# mega328_withheaders_andxbee.net
KiCad netlist of a schematic drawn in EAGLE
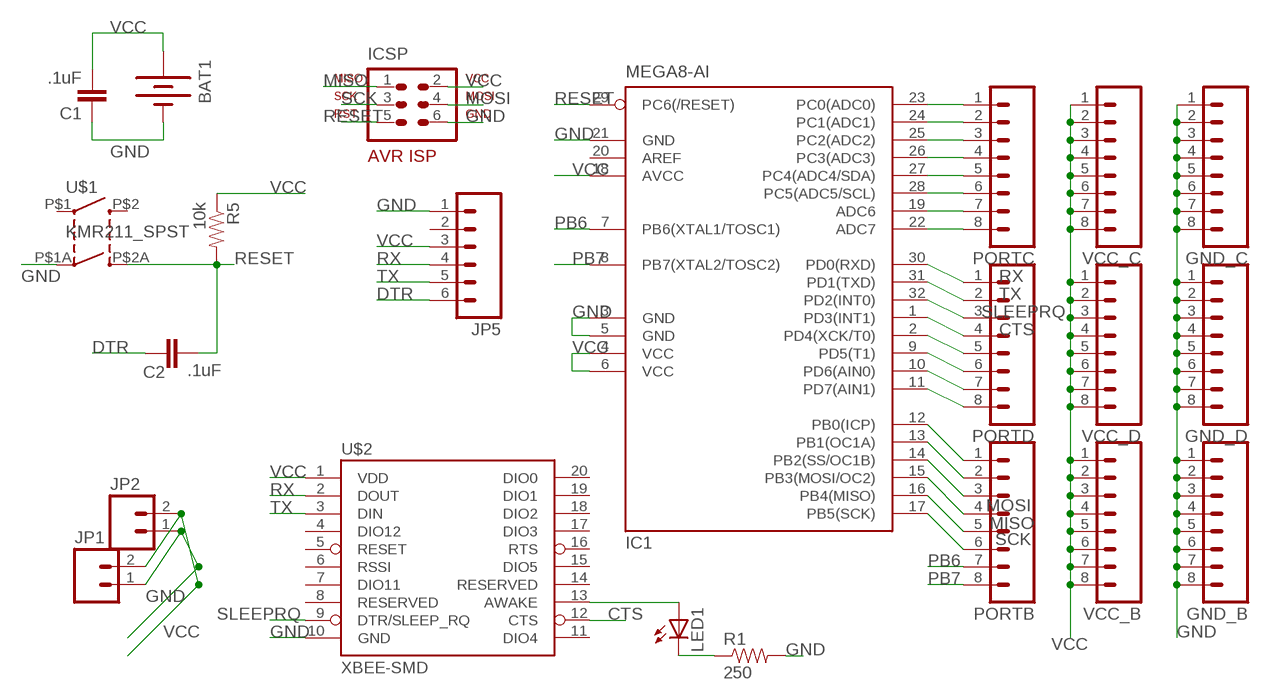
[diagram p0: schematic, sheet 1]

(export (version "E")
  (design (tool "Eeschema 10.0.6"))
  (components
    (comp (ref "BAT1")
      (value "BATTERY20SMD")
      (footprint "eagle-import:BATTCON_20MM")
      (libsource (lib "eagle-import") (part "BATTERY20SMD"))
    )
    (comp (ref "C1")
      (value ".1uF")
      (footprint "eagle-import:0603-CAP")
      (libsource (lib "eagle-import") (part "CAP0603-CAP"))
    )
    (comp (ref "C2")
      (value ".1uF")
      (footprint "eagle-import:0603-CAP")
      (libsource (lib "eagle-import") (part "CAP0603-CAP"))
    )
    (comp (ref "GND_B")
      (value "M081X08")
      (footprint "eagle-import:1X08")
      (libsource (lib "eagle-import") (part "M081X08"))
    )
    (comp (ref "GND_C")
      (value "M081X08")
      (footprint "eagle-import:1X08")
      (libsource (lib "eagle-import") (part "M081X08"))
    )
    (comp (ref "GND_D")
      (value "M081X08")
      (footprint "eagle-import:1X08")
      (libsource (lib "eagle-import") (part "M081X08"))
    )
    (comp (ref "IC1")
      (value "MEGA8-AI")
      (footprint "eagle-import:TQFP32-08")
      (fields (field (name "MPN") "ATMEGA8-16AU"))
      (libsource (lib "eagle-import") (part "MEGA8-AI"))
    )
    (comp (ref "ICSP")
      (value "ISP")
      (footprint "eagle-import:AVR-ISP-6")
      (libsource (lib "eagle-import") (part "AVR-ISP-6VERT"))
    )
    (comp (ref "JP1")
      (value "M02PTH")
      (footprint "eagle-import:1X02")
      (libsource (lib "eagle-import") (part "M02PTH"))
    )
    (comp (ref "JP2")
      (value "M02PTH")
      (footprint "eagle-import:1X02")
      (libsource (lib "eagle-import") (part "M02PTH"))
    )
    (comp (ref "JP5")
      (value "M06SIP")
      (footprint "eagle-import:1X06")
      (libsource (lib "eagle-import") (part "M06SIP"))
    )
    (comp (ref "LED1")
      (value "LEDCHIP-LED0603")
      (footprint "eagle-import:CHIP-LED0603")
      (libsource (lib "eagle-import") (part "LEDCHIP-LED0603"))
    )
    (comp (ref "PORTB")
      (value "M081X08")
      (footprint "eagle-import:1X08")
      (libsource (lib "eagle-import") (part "M081X08"))
    )
    (comp (ref "PORTC")
      (value "M081X08")
      (footprint "eagle-import:1X08")
      (libsource (lib "eagle-import") (part "M081X08"))
    )
    (comp (ref "PORTD")
      (value "M081X08")
      (footprint "eagle-import:1X08")
      (libsource (lib "eagle-import") (part "M081X08"))
    )
    (comp (ref "R1")
      (value "250")
      (footprint "eagle-import:0603-RES")
      (libsource (lib "eagle-import") (part "my library_RESISTOR0603-RES"))
    )
    (comp (ref "R5")
      (value "10k")
      (footprint "eagle-import:0603-RES")
      (libsource (lib "eagle-import") (part "RESISTOR0603-RES"))
    )
    (comp (ref "U$1")
      (value "KMR211_SPST")
      (footprint "eagle-import:KMR211_SPST")
      (libsource (lib "eagle-import") (part "KMR211_SPST"))
    )
    (comp (ref "U$2")
      (value "XBEE-SMD")
      (footprint "eagle-import:XBEE-SMD")
      (libsource (lib "eagle-import") (part "XBEE-SMD"))
    )
    (comp (ref "VCC_B")
      (value "M081X08")
      (footprint "eagle-import:1X08")
      (libsource (lib "eagle-import") (part "M081X08"))
    )
    (comp (ref "VCC_C")
      (value "M081X08")
      (footprint "eagle-import:1X08")
      (libsource (lib "eagle-import") (part "M081X08"))
    )
    (comp (ref "VCC_D")
      (value "M081X08")
      (footprint "eagle-import:1X08")
      (libsource (lib "eagle-import") (part "M081X08"))
    )
  )
  (nets
    (net (code "1") (name "/CTS") (class "Default")
      (node (ref "IC1") (pin "1") (pinfunction "PD3(INT1)_1") (pintype "bidirectional"))
      (node (ref "PORTD") (pin "4") (pinfunction "4_4") (pintype "passive"))
      (node (ref "U$2") (pin "12") (pinfunction "CTS_12") (pintype "output"))
    )
    (net (code "2") (name "/DTR") (class "Default")
      (node (ref "C2") (pin "1") (pinfunction "1_1") (pintype "passive"))
      (node (ref "JP5") (pin "6") (pinfunction "6_6") (pintype "passive"))
    )
    (net (code "3") (name "/GND") (class "Default")
      (node (ref "BAT1") (pin "2") (pinfunction "-_2") (pintype "power_in"))
      (node (ref "C1") (pin "1") (pinfunction "1_1") (pintype "passive"))
      (node (ref "GND_B") (pin "1") (pinfunction "1_1") (pintype "passive"))
      (node (ref "GND_B") (pin "2") (pinfunction "2_2") (pintype "passive"))
      (node (ref "GND_B") (pin "3") (pinfunction "3_3") (pintype "passive"))
      (node (ref "GND_B") (pin "4") (pinfunction "4_4") (pintype "passive"))
      (node (ref "GND_B") (pin "5") (pinfunction "5_5") (pintype "passive"))
      (node (ref "GND_B") (pin "6") (pinfunction "6_6") (pintype "passive"))
      (node (ref "GND_B") (pin "7") (pinfunction "7_7") (pintype "passive"))
      (node (ref "GND_B") (pin "8") (pinfunction "8_8") (pintype "passive"))
      (node (ref "GND_C") (pin "1") (pinfunction "1_1") (pintype "passive"))
      (node (ref "GND_C") (pin "2") (pinfunction "2_2") (pintype "passive"))
      (node (ref "GND_C") (pin "3") (pinfunction "3_3") (pintype "passive"))
      (node (ref "GND_C") (pin "4") (pinfunction "4_4") (pintype "passive"))
      (node (ref "GND_C") (pin "5") (pinfunction "5_5") (pintype "passive"))
      (node (ref "GND_C") (pin "6") (pinfunction "6_6") (pintype "passive"))
      (node (ref "GND_C") (pin "7") (pinfunction "7_7") (pintype "passive"))
      (node (ref "GND_C") (pin "8") (pinfunction "8_8") (pintype "passive"))
      (node (ref "GND_D") (pin "1") (pinfunction "1_1") (pintype "passive"))
      (node (ref "GND_D") (pin "2") (pinfunction "2_2") (pintype "passive"))
      (node (ref "GND_D") (pin "3") (pinfunction "3_3") (pintype "passive"))
      (node (ref "GND_D") (pin "4") (pinfunction "4_4") (pintype "passive"))
      (node (ref "GND_D") (pin "5") (pinfunction "5_5") (pintype "passive"))
      (node (ref "GND_D") (pin "6") (pinfunction "6_6") (pintype "passive"))
      (node (ref "GND_D") (pin "7") (pinfunction "7_7") (pintype "passive"))
      (node (ref "GND_D") (pin "8") (pinfunction "8_8") (pintype "passive"))
      (node (ref "IC1") (pin "21") (pinfunction "GND_21") (pintype "power_in"))
      (node (ref "IC1") (pin "3") (pinfunction "GND_3") (pintype "power_in"))
      (node (ref "IC1") (pin "5") (pinfunction "GND_5") (pintype "power_in"))
      (node (ref "ICSP") (pin "6") (pinfunction "6_6") (pintype "passive"))
      (node (ref "JP1") (pin "1") (pinfunction "1_1") (pintype "passive"))
      (node (ref "JP2") (pin "1") (pinfunction "1_1") (pintype "passive"))
      (node (ref "JP5") (pin "1") (pinfunction "1_1") (pintype "passive"))
      (node (ref "R1") (pin "2") (pinfunction "2_2") (pintype "passive"))
      (node (ref "U$1") (pin "P$1A") (pinfunction "1B_P$1A") (pintype "passive"))
      (node (ref "U$2") (pin "10") (pinfunction "GND_10") (pintype "power_in"))
    )
    (net (code "4") (name "/MISO") (class "Default")
      (node (ref "IC1") (pin "16") (pinfunction "PB4(MISO)_16") (pintype "bidirectional"))
      (node (ref "ICSP") (pin "1") (pinfunction "1_1") (pintype "passive"))
      (node (ref "PORTB") (pin "5") (pinfunction "5_5") (pintype "passive"))
    )
    (net (code "5") (name "/MOSI") (class "Default")
      (node (ref "IC1") (pin "15") (pinfunction "PB3(MOSI/OC2)_15") (pintype "bidirectional"))
      (node (ref "ICSP") (pin "4") (pinfunction "4_4") (pintype "passive"))
      (node (ref "PORTB") (pin "4") (pinfunction "4_4") (pintype "passive"))
    )
    (net (code "6") (name "/PB6") (class "Default")
      (node (ref "IC1") (pin "7") (pinfunction "PB6(XTAL1/TOSC1)_7") (pintype "bidirectional"))
      (node (ref "PORTB") (pin "7") (pinfunction "7_7") (pintype "passive"))
    )
    (net (code "7") (name "/PB7") (class "Default")
      (node (ref "IC1") (pin "8") (pinfunction "PB7(XTAL2/TOSC2)_8") (pintype "bidirectional"))
      (node (ref "PORTB") (pin "8") (pinfunction "8_8") (pintype "passive"))
    )
    (net (code "8") (name "/RESET") (class "Default")
      (node (ref "C2") (pin "2") (pinfunction "2_2") (pintype "passive"))
      (node (ref "IC1") (pin "29") (pinfunction "PC6(/RESET)_29") (pintype "bidirectional"))
      (node (ref "ICSP") (pin "5") (pinfunction "5_5") (pintype "passive"))
      (node (ref "R5") (pin "2") (pinfunction "2_2") (pintype "passive"))
      (node (ref "U$1") (pin "P$2A") (pinfunction "2B_P$2A") (pintype "passive"))
    )
    (net (code "9") (name "/RX") (class "Default")
      (node (ref "IC1") (pin "30") (pinfunction "PD0(RXD)_30") (pintype "bidirectional"))
      (node (ref "JP5") (pin "4") (pinfunction "4_4") (pintype "passive"))
      (node (ref "PORTD") (pin "1") (pinfunction "1_1") (pintype "passive"))
      (node (ref "U$2") (pin "2") (pinfunction "DOUT_2") (pintype "output"))
    )
    (net (code "10") (name "/SCK") (class "Default")
      (node (ref "IC1") (pin "17") (pinfunction "PB5(SCK)_17") (pintype "bidirectional"))
      (node (ref "ICSP") (pin "3") (pinfunction "3_3") (pintype "passive"))
      (node (ref "PORTB") (pin "6") (pinfunction "6_6") (pintype "passive"))
    )
    (net (code "11") (name "/SLEEPRQ") (class "Default")
      (node (ref "IC1") (pin "32") (pinfunction "PD2(INT0)_32") (pintype "bidirectional"))
      (node (ref "PORTD") (pin "3") (pinfunction "3_3") (pintype "passive"))
      (node (ref "U$2") (pin "9") (pinfunction "DTR/SLEEP_RQ_9") (pintype "bidirectional"))
    )
    (net (code "12") (name "/TX") (class "Default")
      (node (ref "IC1") (pin "31") (pinfunction "PD1(TXD)_31") (pintype "bidirectional"))
      (node (ref "JP5") (pin "5") (pinfunction "5_5") (pintype "passive"))
      (node (ref "PORTD") (pin "2") (pinfunction "2_2") (pintype "passive"))
      (node (ref "U$2") (pin "3") (pinfunction "DIN_3") (pintype "input"))
    )
    (net (code "13") (name "/VCC") (class "Default")
      (node (ref "BAT1") (pin "1") (pinfunction "+_1") (pintype "power_in"))
      (node (ref "C1") (pin "2") (pinfunction "2_2") (pintype "passive"))
      (node (ref "IC1") (pin "18") (pinfunction "AVCC_18") (pintype "power_in"))
      (node (ref "IC1") (pin "4") (pinfunction "VCC_4") (pintype "power_in"))
      (node (ref "IC1") (pin "6") (pinfunction "VCC_6") (pintype "power_in"))
      (node (ref "ICSP") (pin "2") (pinfunction "2_2") (pintype "passive"))
      (node (ref "JP1") (pin "2") (pinfunction "2_2") (pintype "passive"))
      (node (ref "JP2") (pin "2") (pinfunction "2_2") (pintype "passive"))
      (node (ref "JP5") (pin "3") (pinfunction "3_3") (pintype "passive"))
      (node (ref "R5") (pin "1") (pinfunction "1_1") (pintype "passive"))
      (node (ref "U$2") (pin "1") (pinfunction "VDD_1") (pintype "power_in"))
      (node (ref "VCC_B") (pin "1") (pinfunction "1_1") (pintype "passive"))
      (node (ref "VCC_B") (pin "2") (pinfunction "2_2") (pintype "passive"))
      (node (ref "VCC_B") (pin "3") (pinfunction "3_3") (pintype "passive"))
      (node (ref "VCC_B") (pin "4") (pinfunction "4_4") (pintype "passive"))
      (node (ref "VCC_B") (pin "5") (pinfunction "5_5") (pintype "passive"))
      (node (ref "VCC_B") (pin "6") (pinfunction "6_6") (pintype "passive"))
      (node (ref "VCC_B") (pin "7") (pinfunction "7_7") (pintype "passive"))
      (node (ref "VCC_B") (pin "8") (pinfunction "8_8") (pintype "passive"))
      (node (ref "VCC_C") (pin "1") (pinfunction "1_1") (pintype "passive"))
      (node (ref "VCC_C") (pin "2") (pinfunction "2_2") (pintype "passive"))
      (node (ref "VCC_C") (pin "3") (pinfunction "3_3") (pintype "passive"))
      (node (ref "VCC_C") (pin "4") (pinfunction "4_4") (pintype "passive"))
      (node (ref "VCC_C") (pin "5") (pinfunction "5_5") (pintype "passive"))
      (node (ref "VCC_C") (pin "6") (pinfunction "6_6") (pintype "passive"))
      (node (ref "VCC_C") (pin "7") (pinfunction "7_7") (pintype "passive"))
      (node (ref "VCC_C") (pin "8") (pinfunction "8_8") (pintype "passive"))
      (node (ref "VCC_D") (pin "1") (pinfunction "1_1") (pintype "passive"))
      (node (ref "VCC_D") (pin "2") (pinfunction "2_2") (pintype "passive"))
      (node (ref "VCC_D") (pin "3") (pinfunction "3_3") (pintype "passive"))
      (node (ref "VCC_D") (pin "4") (pinfunction "4_4") (pintype "passive"))
      (node (ref "VCC_D") (pin "5") (pinfunction "5_5") (pintype "passive"))
      (node (ref "VCC_D") (pin "6") (pinfunction "6_6") (pintype "passive"))
      (node (ref "VCC_D") (pin "7") (pinfunction "7_7") (pintype "passive"))
      (node (ref "VCC_D") (pin "8") (pinfunction "8_8") (pintype "passive"))
    )
    (net (code "14") (name "Net-(IC1-ADC6)") (class "Default")
      (node (ref "IC1") (pin "19") (pinfunction "ADC6_19") (pintype "bidirectional"))
      (node (ref "PORTC") (pin "7") (pinfunction "7_7") (pintype "passive"))
    )
    (net (code "15") (name "Net-(IC1-ADC7)") (class "Default")
      (node (ref "IC1") (pin "22") (pinfunction "ADC7_22") (pintype "bidirectional"))
      (node (ref "PORTC") (pin "8") (pinfunction "8_8") (pintype "passive"))
    )
    (net (code "16") (name "Net-(IC1-PB0(ICP))") (class "Default")
      (node (ref "IC1") (pin "12") (pinfunction "PB0(ICP)_12") (pintype "bidirectional"))
      (node (ref "PORTB") (pin "1") (pinfunction "1_1") (pintype "passive"))
    )
    (net (code "17") (name "Net-(IC1-PB1(OC1A))") (class "Default")
      (node (ref "IC1") (pin "13") (pinfunction "PB1(OC1A)_13") (pintype "bidirectional"))
      (node (ref "PORTB") (pin "2") (pinfunction "2_2") (pintype "passive"))
    )
    (net (code "18") (name "Net-(IC1-PB2(SS{slash}OC1B))") (class "Default")
      (node (ref "IC1") (pin "14") (pinfunction "PB2(SS/OC1B)_14") (pintype "bidirectional"))
      (node (ref "PORTB") (pin "3") (pinfunction "3_3") (pintype "passive"))
    )
    (net (code "19") (name "Net-(IC1-PC0(ADC0))") (class "Default")
      (node (ref "IC1") (pin "23") (pinfunction "PC0(ADC0)_23") (pintype "bidirectional"))
      (node (ref "PORTC") (pin "1") (pinfunction "1_1") (pintype "passive"))
    )
    (net (code "20") (name "Net-(IC1-PC1(ADC1))") (class "Default")
      (node (ref "IC1") (pin "24") (pinfunction "PC1(ADC1)_24") (pintype "bidirectional"))
      (node (ref "PORTC") (pin "2") (pinfunction "2_2") (pintype "passive"))
    )
    (net (code "21") (name "Net-(IC1-PC2(ADC2))") (class "Default")
      (node (ref "IC1") (pin "25") (pinfunction "PC2(ADC2)_25") (pintype "bidirectional"))
      (node (ref "PORTC") (pin "3") (pinfunction "3_3") (pintype "passive"))
    )
    (net (code "22") (name "Net-(IC1-PC3(ADC3))") (class "Default")
      (node (ref "IC1") (pin "26") (pinfunction "PC3(ADC3)_26") (pintype "bidirectional"))
      (node (ref "PORTC") (pin "4") (pinfunction "4_4") (pintype "passive"))
    )
    (net (code "23") (name "Net-(IC1-PC4(ADC4{slash}SDA))") (class "Default")
      (node (ref "IC1") (pin "27") (pinfunction "PC4(ADC4/SDA)_27") (pintype "bidirectional"))
      (node (ref "PORTC") (pin "5") (pinfunction "5_5") (pintype "passive"))
    )
    (net (code "24") (name "Net-(IC1-PC5(ADC5{slash}SCL))") (class "Default")
      (node (ref "IC1") (pin "28") (pinfunction "PC5(ADC5/SCL)_28") (pintype "bidirectional"))
      (node (ref "PORTC") (pin "6") (pinfunction "6_6") (pintype "passive"))
    )
    (net (code "25") (name "Net-(IC1-PD4(XCK{slash}T0))") (class "Default")
      (node (ref "IC1") (pin "2") (pinfunction "PD4(XCK/T0)_2") (pintype "bidirectional"))
      (node (ref "PORTD") (pin "5") (pinfunction "5_5") (pintype "passive"))
    )
    (net (code "26") (name "Net-(IC1-PD5(T1))") (class "Default")
      (node (ref "IC1") (pin "9") (pinfunction "PD5(T1)_9") (pintype "bidirectional"))
      (node (ref "PORTD") (pin "6") (pinfunction "6_6") (pintype "passive"))
    )
    (net (code "27") (name "Net-(IC1-PD6(AIN0))") (class "Default")
      (node (ref "IC1") (pin "10") (pinfunction "PD6(AIN0)_10") (pintype "bidirectional"))
      (node (ref "PORTD") (pin "7") (pinfunction "7_7") (pintype "passive"))
    )
    (net (code "28") (name "Net-(IC1-PD7(AIN1))") (class "Default")
      (node (ref "IC1") (pin "11") (pinfunction "PD7(AIN1)_11") (pintype "bidirectional"))
      (node (ref "PORTD") (pin "8") (pinfunction "8_8") (pintype "passive"))
    )
    (net (code "29") (name "Net-(LED1-PadC)") (class "Default")
      (node (ref "LED1") (pin "C") (pinfunction "C_C") (pintype "passive"))
      (node (ref "R1") (pin "1") (pinfunction "1_1") (pintype "passive"))
    )
    (net (code "30") (name "Net-(U$2-AWAKE)") (class "Default")
      (node (ref "LED1") (pin "A") (pinfunction "A_A") (pintype "passive"))
      (node (ref "U$2") (pin "13") (pinfunction "AWAKE_13") (pintype "bidirectional"))
    )
    (net (code "31") (name "unconnected-(IC1-AREF-Pad20)") (class "Default")
      (node (ref "IC1") (pin "20") (pinfunction "AREF_20") (pintype "passive"))
    )
    (net (code "32") (name "unconnected-(JP5-Pad2)") (class "Default")
      (node (ref "JP5") (pin "2") (pinfunction "2_2") (pintype "passive"))
    )
    (net (code "33") (name "unconnected-(U$1-1A-PadP$1)") (class "Default")
      (node (ref "U$1") (pin "P$1") (pinfunction "1A_P$1") (pintype "no_connect"))
    )
    (net (code "34") (name "unconnected-(U$1-2A-PadP$2)") (class "Default")
      (node (ref "U$1") (pin "P$2") (pinfunction "2A_P$2") (pintype "no_connect"))
    )
    (net (code "35") (name "unconnected-(U$2-DIO0-Pad20)") (class "Default")
      (node (ref "U$2") (pin "20") (pinfunction "DIO0_20") (pintype "bidirectional"))
    )
    (net (code "36") (name "unconnected-(U$2-DIO1-Pad19)") (class "Default")
      (node (ref "U$2") (pin "19") (pinfunction "DIO1_19") (pintype "bidirectional"))
    )
    (net (code "37") (name "unconnected-(U$2-DIO2-Pad18)") (class "Default")
      (node (ref "U$2") (pin "18") (pinfunction "DIO2_18") (pintype "bidirectional"))
    )
    (net (code "38") (name "unconnected-(U$2-DIO3-Pad17)") (class "Default")
      (node (ref "U$2") (pin "17") (pinfunction "DIO3_17") (pintype "bidirectional"))
    )
    (net (code "39") (name "unconnected-(U$2-DIO4-Pad11)") (class "Default")
      (node (ref "U$2") (pin "11") (pinfunction "DIO4_11") (pintype "bidirectional"))
    )
    (net (code "40") (name "unconnected-(U$2-DIO5-Pad15)") (class "Default")
      (node (ref "U$2") (pin "15") (pinfunction "DIO5_15") (pintype "bidirectional"))
    )
    (net (code "41") (name "unconnected-(U$2-DIO11-Pad7)") (class "Default")
      (node (ref "U$2") (pin "7") (pinfunction "DIO11_7") (pintype "bidirectional"))
    )
    (net (code "42") (name "unconnected-(U$2-DIO12-Pad4)") (class "Default")
      (node (ref "U$2") (pin "4") (pinfunction "DIO12_4") (pintype "bidirectional"))
    )
    (net (code "43") (name "unconnected-(U$2-RESERVED-Pad8)") (class "Default")
      (node (ref "U$2") (pin "8") (pinfunction "RESERVED_8") (pintype "bidirectional"))
    )
    (net (code "44") (name "unconnected-(U$2-RESERVED-Pad14)") (class "Default")
      (node (ref "U$2") (pin "14") (pinfunction "RESERVED_14") (pintype "bidirectional"))
    )
    (net (code "45") (name "unconnected-(U$2-RESET-Pad5)") (class "Default")
      (node (ref "U$2") (pin "5") (pinfunction "RESET_5") (pintype "input"))
    )
    (net (code "46") (name "unconnected-(U$2-RSSI-Pad6)") (class "Default")
      (node (ref "U$2") (pin "6") (pinfunction "RSSI_6") (pintype "bidirectional"))
    )
    (net (code "47") (name "unconnected-(U$2-RTS-Pad16)") (class "Default")
      (node (ref "U$2") (pin "16") (pinfunction "RTS_16") (pintype "input"))
    )
  )
)
